# main_board_rev_1.net
KiCad netlist of a schematic drawn in EAGLE
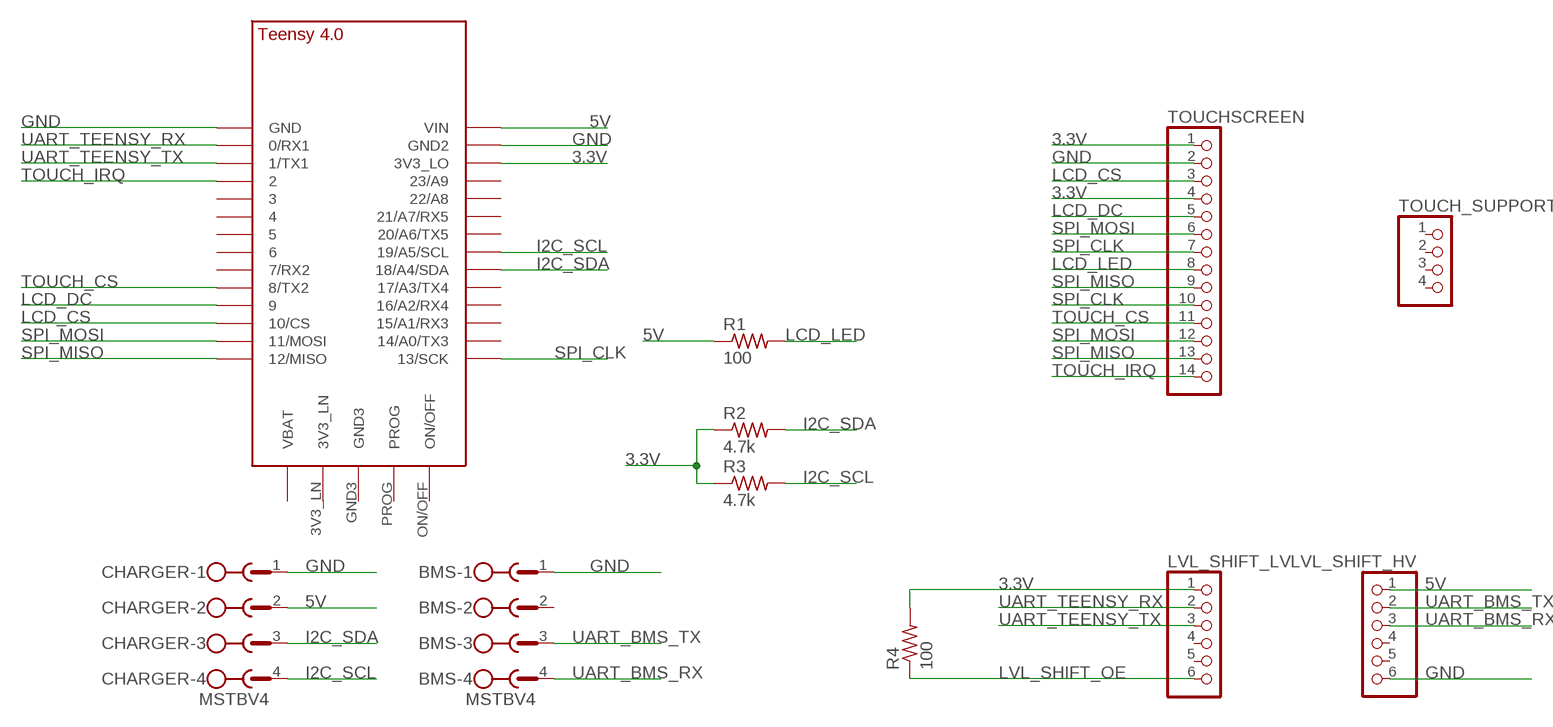
[diagram p0: schematic, sheet 1]

(export (version "E")
  (design (tool "Eeschema 10.0.6"))
  (components
    (comp (ref "BMS")
      (value "MSTBV4")
      (footprint "eagle-import:MSTBV4")
      (fields (field (name "MPN") "MSTBV 2,5/4-GF-5.08"))
      (libsource (lib "eagle-import") (part "MSTBV4"))
    )
    (comp (ref "CHARGER")
      (value "MSTBV4")
      (footprint "eagle-import:MSTBV4")
      (fields (field (name "MPN") "MSTBV 2,5/4-GF-5.08"))
      (libsource (lib "eagle-import") (part "MSTBV4"))
    )
    (comp (ref "LVL_SHIFT_HV")
      (value "PINHD-1X6")
      (footprint "eagle-import:1X06")
      (libsource (lib "eagle-import") (part "PINHD-1X6"))
    )
    (comp (ref "LVL_SHIFT_LV")
      (value "PINHD-1X6")
      (footprint "eagle-import:1X06")
      (libsource (lib "eagle-import") (part "PINHD-1X6"))
    )
    (comp (ref "R1")
      (value "100")
      (footprint "eagle-import:0204_7")
      (libsource (lib "eagle-import") (part "R-US_0204/7"))
    )
    (comp (ref "R2")
      (value "4.7k")
      (footprint "eagle-import:0204_7")
      (libsource (lib "eagle-import") (part "R-US_0204/7"))
    )
    (comp (ref "R3")
      (value "4.7k")
      (footprint "eagle-import:0204_7")
      (libsource (lib "eagle-import") (part "R-US_0204/7"))
    )
    (comp (ref "R4")
      (value "100")
      (footprint "eagle-import:0204_7")
      (libsource (lib "eagle-import") (part "R-US_0204/7"))
    )
    (comp (ref "TOUCHSCREEN")
      (value "PINHD-1X14")
      (footprint "eagle-import:1X14")
      (libsource (lib "eagle-import") (part "PINHD-1X14"))
    )
    (comp (ref "TOUCH_SUPPORT")
      (value "PINHD-1X4")
      (footprint "eagle-import:1X04")
      (libsource (lib "eagle-import") (part "PINHD-1X4"))
    )
    (comp (ref "U$1")
      (value "TEENSY_4.0-BASIC")
      (footprint "eagle-import:TEENSY_4.0-BASIC")
      (libsource (lib "eagle-import") (part "TEENSY_4.0-BASIC"))
    )
  )
  (nets
    (net (code "1") (name "/3.3V") (class "Default")
      (node (ref "LVL_SHIFT_LV") (pin "1") (pinfunction "1_1") (pintype "passive"))
      (node (ref "R2") (pin "1") (pinfunction "1_1") (pintype "passive"))
      (node (ref "R3") (pin "1") (pinfunction "1_1") (pintype "passive"))
      (node (ref "R4") (pin "2") (pinfunction "2_2") (pintype "passive"))
      (node (ref "TOUCHSCREEN") (pin "1") (pinfunction "1_1") (pintype "passive"))
      (node (ref "TOUCHSCREEN") (pin "4") (pinfunction "4_4") (pintype "passive"))
      (node (ref "U$1") (pin "3V3_LO") (pinfunction "3V3_LO_3V3_LO") (pintype "bidirectional"))
    )
    (net (code "2") (name "/5V") (class "Default")
      (node (ref "CHARGER") (pin "2") (pinfunction "1_2") (pintype "passive"))
      (node (ref "LVL_SHIFT_HV") (pin "1") (pinfunction "1_1") (pintype "passive"))
      (node (ref "R1") (pin "1") (pinfunction "1_1") (pintype "passive"))
      (node (ref "U$1") (pin "VIN") (pinfunction "VIN_VIN") (pintype "bidirectional"))
    )
    (net (code "3") (name "/GND") (class "Default")
      (node (ref "BMS") (pin "1") (pinfunction "1_1") (pintype "passive"))
      (node (ref "CHARGER") (pin "1") (pinfunction "1_1") (pintype "passive"))
      (node (ref "LVL_SHIFT_HV") (pin "6") (pinfunction "6_6") (pintype "passive"))
      (node (ref "TOUCHSCREEN") (pin "2") (pinfunction "2_2") (pintype "passive"))
      (node (ref "U$1") (pin "GND") (pinfunction "GND_GND") (pintype "bidirectional"))
      (node (ref "U$1") (pin "GND2") (pinfunction "GND2_GND2") (pintype "bidirectional"))
    )
    (net (code "4") (name "/I2C_SCL") (class "Default")
      (node (ref "CHARGER") (pin "4") (pinfunction "1_4") (pintype "passive"))
      (node (ref "R3") (pin "2") (pinfunction "2_2") (pintype "passive"))
      (node (ref "U$1") (pin "19/A5/SCL") (pinfunction "19/A5/SCL_19/A5/SCL") (pintype "bidirectional"))
    )
    (net (code "5") (name "/I2C_SDA") (class "Default")
      (node (ref "CHARGER") (pin "3") (pinfunction "1_3") (pintype "passive"))
      (node (ref "R2") (pin "2") (pinfunction "2_2") (pintype "passive"))
      (node (ref "U$1") (pin "18/A4/SDA") (pinfunction "18/A4/SDA_18/A4/SDA") (pintype "bidirectional"))
    )
    (net (code "6") (name "/LCD_CS") (class "Default")
      (node (ref "TOUCHSCREEN") (pin "3") (pinfunction "3_3") (pintype "passive"))
      (node (ref "U$1") (pin "10/CS") (pinfunction "10/CS_10/CS") (pintype "bidirectional"))
    )
    (net (code "7") (name "/LCD_DC") (class "Default")
      (node (ref "TOUCHSCREEN") (pin "5") (pinfunction "5_5") (pintype "passive"))
      (node (ref "U$1") (pin "9/CS") (pinfunction "9_9/CS") (pintype "bidirectional"))
    )
    (net (code "8") (name "/LCD_LED") (class "Default")
      (node (ref "R1") (pin "2") (pinfunction "2_2") (pintype "passive"))
      (node (ref "TOUCHSCREEN") (pin "8") (pinfunction "8_8") (pintype "passive"))
    )
    (net (code "9") (name "/LVL_SHIFT_OE") (class "Default")
      (node (ref "LVL_SHIFT_LV") (pin "6") (pinfunction "6_6") (pintype "passive"))
      (node (ref "R4") (pin "1") (pinfunction "1_1") (pintype "passive"))
    )
    (net (code "10") (name "/SPI_CLK") (class "Default")
      (node (ref "TOUCHSCREEN") (pin "10") (pinfunction "10_10") (pintype "passive"))
      (node (ref "TOUCHSCREEN") (pin "7") (pinfunction "7_7") (pintype "passive"))
      (node (ref "U$1") (pin "13/SCK") (pinfunction "13/SCK_13/SCK") (pintype "bidirectional"))
    )
    (net (code "11") (name "/SPI_MISO") (class "Default")
      (node (ref "TOUCHSCREEN") (pin "13") (pinfunction "13_13") (pintype "passive"))
      (node (ref "TOUCHSCREEN") (pin "9") (pinfunction "9_9") (pintype "passive"))
      (node (ref "U$1") (pin "12/MISO") (pinfunction "12/MISO_12/MISO") (pintype "bidirectional"))
    )
    (net (code "12") (name "/SPI_MOSI") (class "Default")
      (node (ref "TOUCHSCREEN") (pin "12") (pinfunction "12_12") (pintype "passive"))
      (node (ref "TOUCHSCREEN") (pin "6") (pinfunction "6_6") (pintype "passive"))
      (node (ref "U$1") (pin "11/MOSI") (pinfunction "11/MOSI_11/MOSI") (pintype "bidirectional"))
    )
    (net (code "13") (name "/TOUCH_CS") (class "Default")
      (node (ref "TOUCHSCREEN") (pin "11") (pinfunction "11_11") (pintype "passive"))
      (node (ref "U$1") (pin "8") (pinfunction "8/TX2_8") (pintype "bidirectional"))
    )
    (net (code "14") (name "/TOUCH_IRQ") (class "Default")
      (node (ref "TOUCHSCREEN") (pin "14") (pinfunction "14_14") (pintype "passive"))
      (node (ref "U$1") (pin "2") (pinfunction "2_2") (pintype "bidirectional"))
    )
    (net (code "15") (name "/UART_BMS_RX") (class "Default")
      (node (ref "BMS") (pin "4") (pinfunction "1_4") (pintype "passive"))
      (node (ref "LVL_SHIFT_HV") (pin "3") (pinfunction "3_3") (pintype "passive"))
    )
    (net (code "16") (name "/UART_BMS_TX") (class "Default")
      (node (ref "BMS") (pin "3") (pinfunction "1_3") (pintype "passive"))
      (node (ref "LVL_SHIFT_HV") (pin "2") (pinfunction "2_2") (pintype "passive"))
    )
    (net (code "17") (name "/UART_TEENSY_RX") (class "Default")
      (node (ref "LVL_SHIFT_LV") (pin "2") (pinfunction "2_2") (pintype "passive"))
      (node (ref "U$1") (pin "0/RX") (pinfunction "0/RX1_0/RX") (pintype "bidirectional"))
    )
    (net (code "18") (name "/UART_TEENSY_TX") (class "Default")
      (node (ref "LVL_SHIFT_LV") (pin "3") (pinfunction "3_3") (pintype "passive"))
      (node (ref "U$1") (pin "1/TX") (pinfunction "1/TX1_1/TX") (pintype "bidirectional"))
    )
    (net (code "19") (name "unconnected-(BMSB-1-Pad2)") (class "Default")
      (node (ref "BMS") (pin "2") (pinfunction "1_2") (pintype "passive"))
    )
    (net (code "20") (name "unconnected-(LVL_SHIFT_HV-Pad4)") (class "Default")
      (node (ref "LVL_SHIFT_HV") (pin "4") (pinfunction "4_4") (pintype "passive"))
    )
    (net (code "21") (name "unconnected-(LVL_SHIFT_HV-Pad5)") (class "Default")
      (node (ref "LVL_SHIFT_HV") (pin "5") (pinfunction "5_5") (pintype "passive"))
    )
    (net (code "22") (name "unconnected-(LVL_SHIFT_LV-Pad4)") (class "Default")
      (node (ref "LVL_SHIFT_LV") (pin "4") (pinfunction "4_4") (pintype "passive"))
    )
    (net (code "23") (name "unconnected-(LVL_SHIFT_LV-Pad5)") (class "Default")
      (node (ref "LVL_SHIFT_LV") (pin "5") (pinfunction "5_5") (pintype "passive"))
    )
    (net (code "24") (name "unconnected-(TOUCH_SUPPORT-Pad1)") (class "Default")
      (node (ref "TOUCH_SUPPORT") (pin "1") (pinfunction "1_1") (pintype "passive"))
    )
    (net (code "25") (name "unconnected-(TOUCH_SUPPORT-Pad2)") (class "Default")
      (node (ref "TOUCH_SUPPORT") (pin "2") (pinfunction "2_2") (pintype "passive"))
    )
    (net (code "26") (name "unconnected-(TOUCH_SUPPORT-Pad3)") (class "Default")
      (node (ref "TOUCH_SUPPORT") (pin "3") (pinfunction "3_3") (pintype "passive"))
    )
    (net (code "27") (name "unconnected-(TOUCH_SUPPORT-Pad4)") (class "Default")
      (node (ref "TOUCH_SUPPORT") (pin "4") (pinfunction "4_4") (pintype "passive"))
    )
    (net (code "28") (name "unconnected-(U$1-3-Pad3{slash}CANTX)") (class "Default")
      (node (ref "U$1") (pin "3/CANTX") (pinfunction "3_3/CANTX") (pintype "bidirectional"))
    )
    (net (code "29") (name "unconnected-(U$1-4-Pad4{slash}CANRX)") (class "Default")
      (node (ref "U$1") (pin "4/CANRX") (pinfunction "4_4/CANRX") (pintype "bidirectional"))
    )
    (net (code "30") (name "unconnected-(U$1-7{slash}RX2-Pad7)") (class "Default")
      (node (ref "U$1") (pin "7") (pinfunction "7/RX2_7") (pintype "bidirectional"))
    )
    (net (code "31") (name "unconnected-(U$1-14{slash}A0{slash}TX3-Pad14{slash}A0)") (class "Default")
      (node (ref "U$1") (pin "14/A0") (pinfunction "14/A0/TX3_14/A0") (pintype "bidirectional"))
    )
    (net (code "32") (name "unconnected-(U$1-15{slash}A1{slash}RX3-Pad15{slash}A1)") (class "Default")
      (node (ref "U$1") (pin "15/A1") (pinfunction "15/A1/RX3_15/A1") (pintype "bidirectional"))
    )
    (net (code "33") (name "unconnected-(U$1-16{slash}A2{slash}RX4-Pad16{slash}A2)") (class "Default")
      (node (ref "U$1") (pin "16/A2") (pinfunction "16/A2/RX4_16/A2") (pintype "bidirectional"))
    )
    (net (code "34") (name "unconnected-(U$1-17{slash}A3{slash}TX4-Pad17{slash}A3)") (class "Default")
      (node (ref "U$1") (pin "17/A3") (pinfunction "17/A3/TX4_17/A3") (pintype "bidirectional"))
    )
    (net (code "35") (name "unconnected-(U$1-20{slash}A6{slash}TX5-Pad20{slash}A6)") (class "Default")
      (node (ref "U$1") (pin "20/A6") (pinfunction "20/A6/TX5_20/A6") (pintype "bidirectional"))
    )
    (net (code "36") (name "unconnected-(U$1-21{slash}A7{slash}RX5-Pad21{slash}A7)") (class "Default")
      (node (ref "U$1") (pin "21/A7") (pinfunction "21/A7/RX5_21/A7") (pintype "bidirectional"))
    )
    (net (code "37") (name "unconnected-(U$1-Pad3V3_LN)") (class "Default")
      (node (ref "U$1") (pin "3V3_LN") (pinfunction "3V3_LN_3V3_LN") (pintype "bidirectional"))
    )
    (net (code "38") (name "unconnected-(U$1-Pad5)") (class "Default")
      (node (ref "U$1") (pin "5") (pinfunction "5_5") (pintype "bidirectional"))
    )
    (net (code "39") (name "unconnected-(U$1-Pad6)") (class "Default")
      (node (ref "U$1") (pin "6") (pinfunction "6_6") (pintype "bidirectional"))
    )
    (net (code "40") (name "unconnected-(U$1-Pad22{slash}A8)") (class "Default")
      (node (ref "U$1") (pin "22/A8") (pinfunction "22/A8_22/A8") (pintype "bidirectional"))
    )
    (net (code "41") (name "unconnected-(U$1-Pad23{slash}A9)") (class "Default")
      (node (ref "U$1") (pin "23/A9") (pinfunction "23/A9_23/A9") (pintype "bidirectional"))
    )
    (net (code "42") (name "unconnected-(U$1-PadGND3)") (class "Default")
      (node (ref "U$1") (pin "GND3") (pinfunction "GND3_GND3") (pintype "bidirectional"))
    )
    (net (code "43") (name "unconnected-(U$1-PadON{slash}OFF)") (class "Default")
      (node (ref "U$1") (pin "ON/OFF") (pinfunction "ON/OFF_ON/OFF") (pintype "bidirectional"))
    )
    (net (code "44") (name "unconnected-(U$1-PadPROG)") (class "Default")
      (node (ref "U$1") (pin "PROG") (pinfunction "PROG_PROG") (pintype "bidirectional"))
    )
    (net (code "45") (name "unconnected-(U$1-VBAT-PadVBAT\\)") (class "Default")
      (node (ref "U$1") (pin "VBAT\\") (pinfunction "VBAT_VBAT\\") (pintype "bidirectional"))
    )
  )
)
